# Master_2.net
KiCad netlist of a schematic drawn in Altium Designer
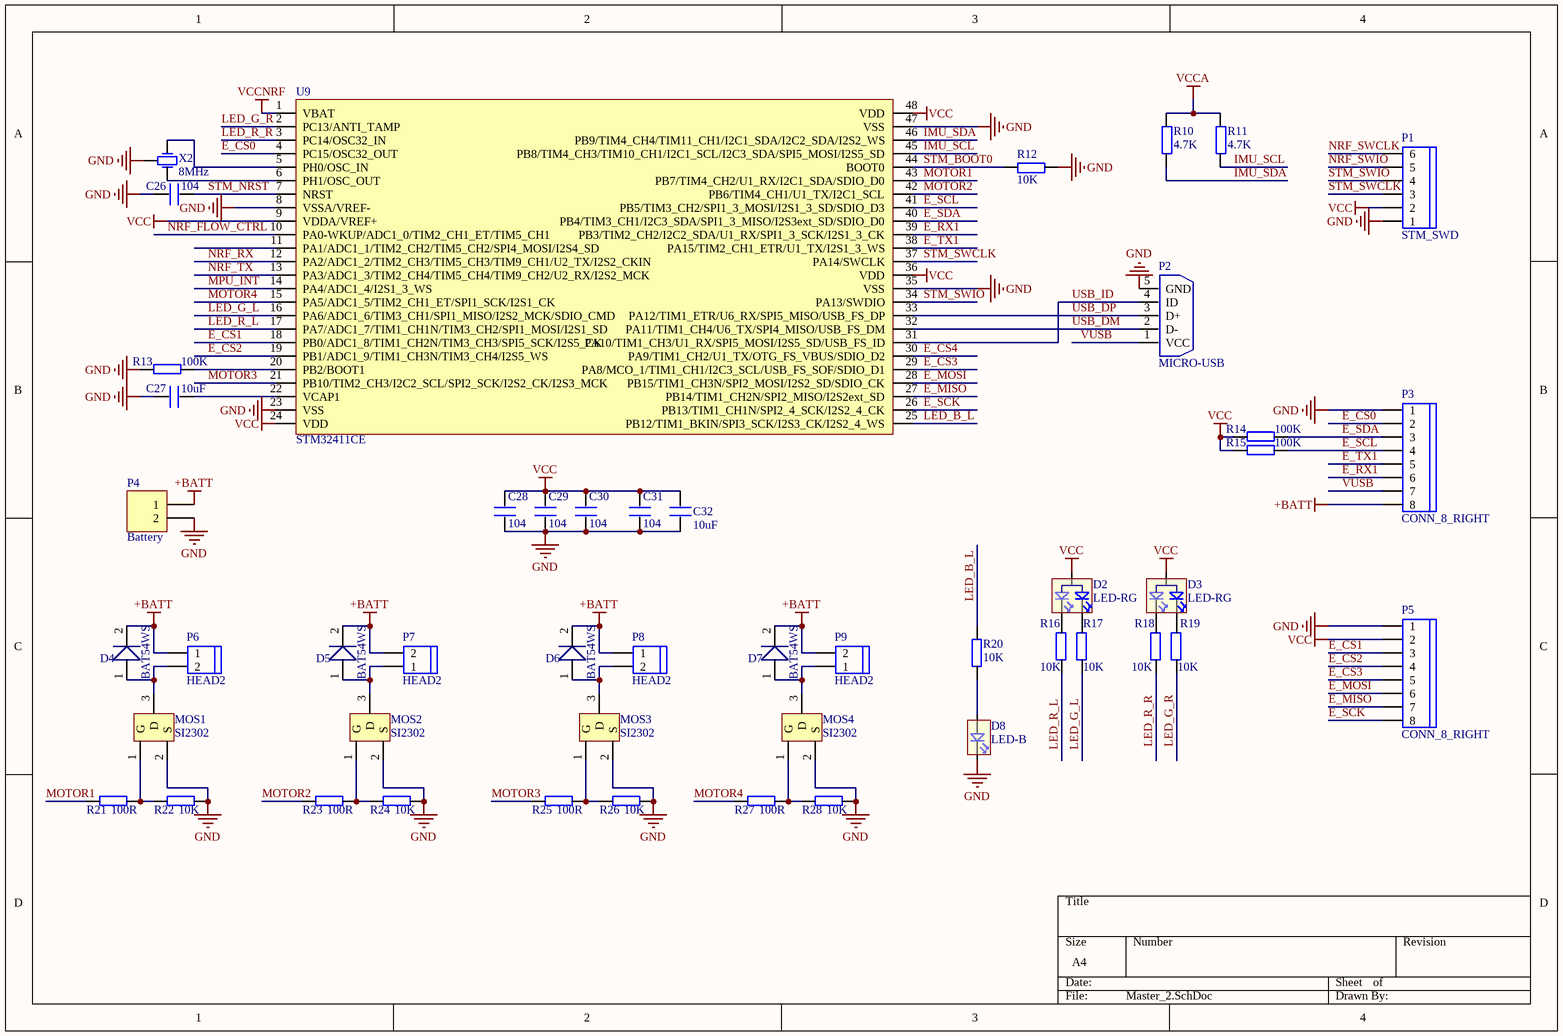
[diagram p0: Master_2.SchDoc]

(export (version "E")
  (design (tool "Eeschema 10.0.6"))
  (components
    (comp (ref "C26") (value "104") (footprint "0402") (libsource (lib "MiniFly ") (part "C")))
    (comp (ref "C27") (value "10uF") (footprint "0603P") (libsource (lib "MiniFly ") (part "C")))
    (comp (ref "C28") (value "104") (footprint "0402") (libsource (lib "MiniFly ") (part "C")))
    (comp (ref "C29") (value "104") (footprint "0402") (libsource (lib "MiniFly ") (part "C")))
    (comp (ref "C30") (value "104") (footprint "0402") (libsource (lib "MiniFly ") (part "C")))
    (comp (ref "C31") (value "104") (footprint "0402") (libsource (lib "MiniFly ") (part "C")))
    (comp (ref "C32") (value "10uF") (footprint "0603P") (libsource (lib "MiniFly ") (part "C")))
    (comp (ref "D2")
      (value "LED-RG")
      (footprint "LED1206  侧贴")
      (description "LED 1206 侧贴 双色")
      (libsource (lib "MiniFly ") (part "LED 1206 侧贴 双色"))
    )
    (comp (ref "D3")
      (value "LED-RG")
      (footprint "LED1206  侧贴")
      (description "LED 1206 侧贴 双色")
      (libsource (lib "MiniFly ") (part "LED 1206 侧贴 双色"))
    )
    (comp (ref "D4")
      (value "BAT54WS")
      (footprint "SOD-323")
      (description "单肖特基二极管")
      (libsource (lib "MiniFly ") (part "BAT54"))
    )
    (comp (ref "D5")
      (value "BAT54WS")
      (footprint "SOD-323")
      (description "单肖特基二极管")
      (libsource (lib "MiniFly ") (part "BAT54"))
    )
    (comp (ref "D6")
      (value "BAT54WS")
      (footprint "SOD-323")
      (description "单肖特基二极管")
      (libsource (lib "MiniFly ") (part "BAT54"))
    )
    (comp (ref "D7")
      (value "BAT54WS")
      (footprint "SOD-323")
      (description "单肖特基二极管")
      (libsource (lib "MiniFly ") (part "BAT54"))
    )
    (comp (ref "D8")
      (value "LED-B")
      (footprint "LED1206  侧贴")
      (description "LED 1206 侧贴  单色")
      (libsource (lib "MiniFly ") (part "LED 1206 侧贴  单色"))
    )
    (comp (ref "MOS1")
      (value "SI2302")
      (footprint "SO-G3/C2.5")
      (description "AP2306")
      (libsource (lib "MiniFly ") (part "MOS-N"))
    )
    (comp (ref "MOS2")
      (value "SI2302")
      (footprint "SO-G3/C2.5")
      (description "AP2306")
      (libsource (lib "MiniFly ") (part "MOS-N"))
    )
    (comp (ref "MOS3")
      (value "SI2302")
      (footprint "SO-G3/C2.5")
      (description "AP2306")
      (libsource (lib "MiniFly ") (part "MOS-N"))
    )
    (comp (ref "MOS4")
      (value "SI2302")
      (footprint "SO-G3/C2.5")
      (description "AP2306")
      (libsource (lib "MiniFly ") (part "MOS-N"))
    )
    (comp (ref "P1") (value "STM_SWD") (footprint "SH1.0-6P") (libsource (lib "MiniFly ") (part "HEAD6")))
    (comp (ref "P2")
      (value "MICRO-USB")
      (footprint "MICRO_USB5P_SOP")
      (libsource (lib "MiniFly ") (part "USB5"))
    )
    (comp (ref "P3")
      (value "CONN_8_RIGHT")
      (footprint "HEADER8-2.0MM-SMD")
      (libsource (lib "MiniFly ") (part "HEAD8"))
    )
    (comp (ref "P4")
      (value "Battery")
      (footprint "HDR1X2")
      (description "Header, 2-Pin")
      (fields (field (name "PUBLISHER") "Altium Limited"))
      (libsource (lib "MiniFly ") (part "Header 2"))
    )
    (comp (ref "P5")
      (value "CONN_8_RIGHT")
      (footprint "HEADER8-2.0MM-SMD")
      (libsource (lib "MiniFly ") (part "HEAD8"))
    )
    (comp (ref "P6") (value "HEAD2") (footprint "HEADER2-1.25MM") (libsource (lib "MiniFly ") (part "HEAD2")))
    (comp (ref "P7") (value "HEAD2") (footprint "HEADER2-1.25MM") (libsource (lib "MiniFly ") (part "HEAD2")))
    (comp (ref "P8") (value "HEAD2") (footprint "HEADER2-1.25MM") (libsource (lib "MiniFly ") (part "HEAD2")))
    (comp (ref "P9") (value "HEAD2") (footprint "HEADER2-1.25MM") (libsource (lib "MiniFly ") (part "HEAD2")))
    (comp (ref "R10") (value "4.7K") (footprint "0402") (libsource (lib "MiniFly ") (part "R")))
    (comp (ref "R11") (value "4.7K") (footprint "0402") (libsource (lib "MiniFly ") (part "R")))
    (comp (ref "R12") (value "10K") (footprint "0402") (libsource (lib "MiniFly ") (part "R")))
    (comp (ref "R13") (value "100K") (footprint "0402") (libsource (lib "MiniFly ") (part "R")))
    (comp (ref "R14") (value "100K") (footprint "0402") (libsource (lib "MiniFly ") (part "R")))
    (comp (ref "R15") (value "100K") (footprint "0402") (libsource (lib "MiniFly ") (part "R")))
    (comp (ref "R16") (value "10K") (footprint "0402") (libsource (lib "MiniFly ") (part "R")))
    (comp (ref "R17") (value "10K") (footprint "0402") (libsource (lib "MiniFly ") (part "R")))
    (comp (ref "R18") (value "10K") (footprint "0402") (libsource (lib "MiniFly ") (part "R")))
    (comp (ref "R19") (value "10K") (footprint "0402") (libsource (lib "MiniFly ") (part "R")))
    (comp (ref "R20") (value "10K") (footprint "0402") (libsource (lib "MiniFly ") (part "R")))
    (comp (ref "R21") (value "100R") (footprint "0402") (libsource (lib "MiniFly ") (part "R")))
    (comp (ref "R22") (value "10K") (footprint "0402") (libsource (lib "MiniFly ") (part "R")))
    (comp (ref "R23") (value "100R") (footprint "0402") (libsource (lib "MiniFly ") (part "R")))
    (comp (ref "R24") (value "10K") (footprint "0402") (libsource (lib "MiniFly ") (part "R")))
    (comp (ref "R25") (value "100R") (footprint "0402") (libsource (lib "MiniFly ") (part "R")))
    (comp (ref "R26") (value "10K") (footprint "0402") (libsource (lib "MiniFly ") (part "R")))
    (comp (ref "R27") (value "100R") (footprint "0402") (libsource (lib "MiniFly ") (part "R")))
    (comp (ref "R28") (value "10K") (footprint "0402") (libsource (lib "MiniFly ") (part "R")))
    (comp (ref "U9")
      (value "STM32411CE")
      (footprint "UFQFPN48")
      (description "STM32411xC_xE")
      (libsource (lib "MiniFly ") (part "STM32F411xC_xE"))
    )
    (comp (ref "X2") (value "8MHz") (footprint "XTAL3215") (libsource (lib "MiniFly ") (part "XTAL-3215")))
  )
  (nets
    (net (code "1") (name "+BATT") (class "Default")
      (node (ref "D4") (pin "2") (pinfunction "2_2") (pintype "passive"))
      (node (ref "D5") (pin "2") (pinfunction "2_2") (pintype "passive"))
      (node (ref "D6") (pin "2") (pinfunction "2_2") (pintype "passive"))
      (node (ref "D7") (pin "2") (pinfunction "2_2") (pintype "passive"))
      (node (ref "P3") (pin "8") (pinfunction "8_8") (pintype "passive"))
      (node (ref "P4") (pin "1") (pinfunction "1_1") (pintype "passive"))
      (node (ref "P6") (pin "1") (pinfunction "1_1") (pintype "passive"))
      (node (ref "P7") (pin "2") (pinfunction "2_2") (pintype "passive"))
      (node (ref "P8") (pin "1") (pinfunction "1_1") (pintype "passive"))
      (node (ref "P9") (pin "2") (pinfunction "2_2") (pintype "passive"))
    )
    (net (code "2") (name "/E_CS0") (class "Default")
      (node (ref "P3") (pin "2") (pinfunction "2_2") (pintype "passive"))
      (node (ref "U9") (pin "4") (pinfunction "PC15/OSC32_OUT_4") (pintype "passive"))
    )
    (net (code "3") (name "/E_CS1") (class "Default")
      (node (ref "P5") (pin "3") (pinfunction "3_3") (pintype "passive"))
      (node (ref "U9") (pin "18") (pinfunction "PB0/ADC1_8/TIM1_CH2N/TIM3_CH3/SPI5_SCK/I2S5_CK_18") (pintype "passive"))
    )
    (net (code "4") (name "/E_CS2") (class "Default")
      (node (ref "P5") (pin "4") (pinfunction "4_4") (pintype "passive"))
      (node (ref "U9") (pin "19") (pinfunction "PB1/ADC1_9/TIM1_CH3N/TIM3_CH4/I2S5_WS_19") (pintype "passive"))
    )
    (net (code "5") (name "/E_CS3") (class "Default")
      (node (ref "P5") (pin "5") (pinfunction "5_5") (pintype "passive"))
      (node (ref "U9") (pin "29") (pinfunction "PA8/MCO_1/TIM1_CH1/I2C3_SCL/USB_FS_SOF/SDIO_D1_29") (pintype "passive"))
    )
    (net (code "6") (name "/E_CS4") (class "Default")
      (node (ref "U9") (pin "30") (pinfunction "PA9/TIM1_CH2/U1_TX/OTG_FS_VBUS/SDIO_D2_30") (pintype "passive"))
    )
    (net (code "7") (name "/E_MISO") (class "Default")
      (node (ref "P5") (pin "7") (pinfunction "7_7") (pintype "passive"))
      (node (ref "U9") (pin "27") (pinfunction "PB14/TIM1_CH2N/SPI2_MISO/I2S2ext_SD_27") (pintype "passive"))
    )
    (net (code "8") (name "/E_MOSI") (class "Default")
      (node (ref "P5") (pin "6") (pinfunction "6_6") (pintype "passive"))
      (node (ref "U9") (pin "28") (pinfunction "PB15/TIM1_CH3N/SPI2_MOSI/I2S2_SD/SDIO_CK_28") (pintype "passive"))
    )
    (net (code "9") (name "/E_RX1") (class "Default")
      (node (ref "P3") (pin "6") (pinfunction "6_6") (pintype "passive"))
      (node (ref "U9") (pin "39") (pinfunction "PB3/TIM2_CH2/I2C2_SDA/U1_RX/SPI1_3_SCK/I2S1_3_CK_39") (pintype "passive"))
    )
    (net (code "10") (name "/E_SCK") (class "Default")
      (node (ref "P5") (pin "8") (pinfunction "8_8") (pintype "passive"))
      (node (ref "U9") (pin "26") (pinfunction "PB13/TIM1_CH1N/SPI2_4_SCK/I2S2_4_CK_26") (pintype "passive"))
    )
    (net (code "11") (name "/E_SCL") (class "Default")
      (node (ref "P3") (pin "4") (pinfunction "4_4") (pintype "passive"))
      (node (ref "R15") (pin "1") (pintype "passive"))
      (node (ref "U9") (pin "41") (pinfunction "PB5/TIM3_CH2/SPI1_3_MOSI/I2S1_3_SD/SDIO_D3_41") (pintype "passive"))
    )
    (net (code "12") (name "/E_SDA") (class "Default")
      (node (ref "P3") (pin "3") (pinfunction "3_3") (pintype "passive"))
      (node (ref "R14") (pin "1") (pintype "passive"))
      (node (ref "U9") (pin "40") (pinfunction "PB4/TIM3_CH1/I2C3_SDA/SPI1_3_MISO/I2S3ext_SD/SDIO_D0_40") (pintype "passive"))
    )
    (net (code "13") (name "/E_TX1") (class "Default")
      (node (ref "P3") (pin "5") (pinfunction "5_5") (pintype "passive"))
      (node (ref "U9") (pin "38") (pinfunction "PA15/TIM2_CH1_ETR/U1_TX/I2S1_3_WS_38") (pintype "passive"))
    )
    (net (code "14") (name "/IMU_SCL") (class "Default")
      (node (ref "R11") (pin "1") (pintype "passive"))
      (node (ref "U9") (pin "45") (pinfunction "PB8/TIM4_CH3/TIM10_CH1/I2C1_SCL/I2C3_SDA/SPI5_MOSI/I2S5_SD_45") (pintype "passive"))
    )
    (net (code "15") (name "/IMU_SDA") (class "Default")
      (node (ref "R10") (pin "1") (pintype "passive"))
      (node (ref "U9") (pin "46") (pinfunction "PB9/TIM4_CH4/TIM11_CH1/I2C1_SDA/I2C2_SDA/I2S2_WS_46") (pintype "passive"))
    )
    (net (code "16") (name "/LED_B_L") (class "Default")
      (node (ref "R20") (pin "1") (pintype "passive"))
      (node (ref "U9") (pin "25") (pinfunction "PB12/TIM1_BKIN/SPI3_SCK/I2S3_CK/I2S2_4_WS_25") (pintype "passive"))
    )
    (net (code "17") (name "/LED_G_L") (class "Default")
      (node (ref "R17") (pin "2") (pintype "passive"))
      (node (ref "U9") (pin "16") (pinfunction "PA6/ADC1_6/TIM3_CH1/SPI1_MISO/I2S2_MCK/SDIO_CMD_16") (pintype "passive"))
    )
    (net (code "18") (name "/LED_G_R") (class "Default")
      (node (ref "R19") (pin "2") (pintype "passive"))
      (node (ref "U9") (pin "2") (pinfunction "PC13/ANTI_TAMP_2") (pintype "passive"))
    )
    (net (code "19") (name "/LED_R_L") (class "Default")
      (node (ref "R16") (pin "2") (pintype "passive"))
      (node (ref "U9") (pin "17") (pinfunction "PA7/ADC1_7/TIM1_CH1N/TIM3_CH2/SPI1_MOSI/I2S1_SD_17") (pintype "passive"))
    )
    (net (code "20") (name "/LED_R_R") (class "Default")
      (node (ref "R18") (pin "2") (pintype "passive"))
      (node (ref "U9") (pin "3") (pinfunction "PC14/OSC32_IN_3") (pintype "passive"))
    )
    (net (code "21") (name "/MOTOR1") (class "Default")
      (node (ref "R21") (pin "2") (pintype "passive"))
      (node (ref "U9") (pin "43") (pinfunction "PB7/TIM4_CH2/U1_RX/I2C1_SDA/SDIO_D0_43") (pintype "passive"))
    )
    (net (code "22") (name "/MOTOR2") (class "Default")
      (node (ref "R23") (pin "2") (pintype "passive"))
      (node (ref "U9") (pin "42") (pinfunction "PB6/TIM4_CH1/U1_TX/I2C1_SCL_42") (pintype "passive"))
    )
    (net (code "23") (name "/MOTOR3") (class "Default")
      (node (ref "R25") (pin "2") (pintype "passive"))
      (node (ref "U9") (pin "21") (pinfunction "PB10/TIM2_CH3/I2C2_SCL/SPI2_SCK/I2S2_CK/I2S3_MCK_21") (pintype "passive"))
    )
    (net (code "24") (name "/MOTOR4") (class "Default")
      (node (ref "R27") (pin "2") (pintype "passive"))
      (node (ref "U9") (pin "15") (pinfunction "PA5/ADC1_5/TIM2_CH1_ET/SPI1_SCK/I2S1_CK_15") (pintype "passive"))
    )
    (net (code "25") (name "/MPU_INT") (class "Default")
      (node (ref "U9") (pin "14") (pinfunction "PA4/ADC1_4/I2S1_3_WS_14") (pintype "passive"))
    )
    (net (code "26") (name "/NRF_FLOW_CTRL") (class "Default")
      (node (ref "U9") (pin "10") (pinfunction "PA0-WKUP/ADC1_0/TIM2_CH1_ET/TIM5_CH1_10") (pintype "passive"))
    )
    (net (code "27") (name "/NRF_RX") (class "Default")
      (node (ref "U9") (pin "12") (pinfunction "PA2/ADC1_2/TIM2_CH3/TIM5_CH3/TIM9_CH1/U2_TX/I2S2_CKIN_12") (pintype "passive"))
    )
    (net (code "28") (name "/NRF_SWCLK") (class "Default")
      (node (ref "P1") (pin "6") (pinfunction "6_6") (pintype "passive"))
    )
    (net (code "29") (name "/NRF_SWIO") (class "Default")
      (node (ref "P1") (pin "5") (pinfunction "5_5") (pintype "passive"))
    )
    (net (code "30") (name "/NRF_TX") (class "Default")
      (node (ref "U9") (pin "13") (pinfunction "PA3/ADC1_3/TIM2_CH4/TIM5_CH4/TIM9_CH2/U2_RX/I2S2_MCK_13") (pintype "passive"))
    )
    (net (code "31") (name "/STM_BOOT0") (class "Default")
      (node (ref "R12") (pin "1") (pintype "passive"))
      (node (ref "U9") (pin "44") (pinfunction "BOOT0_44") (pintype "passive"))
    )
    (net (code "32") (name "/STM_NRST") (class "Default")
      (node (ref "C26") (pin "2") (pintype "passive"))
      (node (ref "U9") (pin "7") (pinfunction "NRST_7") (pintype "passive"))
    )
    (net (code "33") (name "/STM_SWCLK") (class "Default")
      (node (ref "P1") (pin "3") (pinfunction "3_3") (pintype "passive"))
      (node (ref "U9") (pin "37") (pinfunction "PA14/SWCLK_37") (pintype "passive"))
    )
    (net (code "34") (name "/STM_SWIO") (class "Default")
      (node (ref "P1") (pin "4") (pinfunction "4_4") (pintype "passive"))
      (node (ref "U9") (pin "34") (pinfunction "PA13/SWDIO_34") (pintype "passive"))
    )
    (net (code "35") (name "/USB_DM") (class "Default")
      (node (ref "P2") (pin "2") (pinfunction "D-_2") (pintype "passive"))
      (node (ref "U9") (pin "32") (pinfunction "PA11/TIM1_CH4/U6_TX/SPI4_MISO/USB_FS_DM_32") (pintype "passive"))
    )
    (net (code "36") (name "/USB_DP") (class "Default")
      (node (ref "P2") (pin "3") (pinfunction "D+_3") (pintype "passive"))
      (node (ref "U9") (pin "33") (pinfunction "PA12/TIM1_ETR/U6_RX/SPI5_MISO/USB_FS_DP_33") (pintype "passive"))
    )
    (net (code "37") (name "/USB_ID") (class "Default")
      (node (ref "P2") (pin "4") (pinfunction "ID_4") (pintype "passive"))
      (node (ref "U9") (pin "31") (pinfunction "PA10/TIM1_CH3/U1_RX/SPI5_MOSI/I2S5_SD/USB_FS_ID_31") (pintype "passive"))
    )
    (net (code "38") (name "/VUSB") (class "Default")
      (node (ref "P2") (pin "1") (pinfunction "VCC_1") (pintype "passive"))
      (node (ref "P3") (pin "7") (pinfunction "7_7") (pintype "passive"))
    )
    (net (code "39") (name "GND") (class "Default")
      (node (ref "C26") (pin "1") (pintype "passive"))
      (node (ref "C27") (pin "1") (pintype "passive"))
      (node (ref "C28") (pin "1") (pintype "passive"))
      (node (ref "C29") (pin "1") (pintype "passive"))
      (node (ref "C30") (pin "1") (pintype "passive"))
      (node (ref "C31") (pin "1") (pintype "passive"))
      (node (ref "C32") (pin "1") (pintype "passive"))
      (node (ref "D8") (pin "1") (pinfunction "1_1") (pintype "passive"))
      (node (ref "MOS1") (pin "2") (pinfunction "S_2") (pintype "passive"))
      (node (ref "MOS2") (pin "2") (pinfunction "S_2") (pintype "passive"))
      (node (ref "MOS3") (pin "2") (pinfunction "S_2") (pintype "passive"))
      (node (ref "MOS4") (pin "2") (pinfunction "S_2") (pintype "passive"))
      (node (ref "P1") (pin "1") (pinfunction "1_1") (pintype "passive"))
      (node (ref "P2") (pin "5") (pinfunction "GND_5") (pintype "passive"))
      (node (ref "P3") (pin "1") (pinfunction "1_1") (pintype "passive"))
      (node (ref "P4") (pin "2") (pinfunction "2_2") (pintype "passive"))
      (node (ref "P5") (pin "1") (pinfunction "1_1") (pintype "passive"))
      (node (ref "R12") (pin "2") (pintype "passive"))
      (node (ref "R13") (pin "2") (pintype "passive"))
      (node (ref "R22") (pin "1") (pintype "passive"))
      (node (ref "R24") (pin "1") (pintype "passive"))
      (node (ref "R26") (pin "1") (pintype "passive"))
      (node (ref "R28") (pin "1") (pintype "passive"))
      (node (ref "U9") (pin "23") (pinfunction "VSS_23") (pintype "passive"))
      (node (ref "U9") (pin "35") (pinfunction "VSS_35") (pintype "passive"))
      (node (ref "U9") (pin "47") (pinfunction "VSS_47") (pintype "passive"))
      (node (ref "U9") (pin "8") (pinfunction "VSSA/VREF-_8") (pintype "passive"))
      (node (ref "X2") (pin "2") (pinfunction "GND_2") (pintype "passive"))
    )
    (net (code "40") (name "Net-(D2-Pad1)") (class "Default")
      (node (ref "D2") (pin "1") (pinfunction "1_1") (pintype "passive"))
      (node (ref "R16") (pin "1") (pintype "passive"))
    )
    (net (code "41") (name "Net-(D2-Pad2)") (class "Default")
      (node (ref "D2") (pin "2") (pinfunction "2_2") (pintype "passive"))
      (node (ref "R17") (pin "1") (pintype "passive"))
    )
    (net (code "42") (name "Net-(D3-Pad1)") (class "Default")
      (node (ref "D3") (pin "1") (pinfunction "1_1") (pintype "passive"))
      (node (ref "R18") (pin "1") (pintype "passive"))
    )
    (net (code "43") (name "Net-(D3-Pad2)") (class "Default")
      (node (ref "D3") (pin "2") (pinfunction "2_2") (pintype "passive"))
      (node (ref "R19") (pin "1") (pintype "passive"))
    )
    (net (code "44") (name "Net-(D8-Pad3)") (class "Default")
      (node (ref "D8") (pin "3") (pinfunction "3_3") (pintype "passive"))
      (node (ref "R20") (pin "2") (pintype "passive"))
    )
    (net (code "45") (name "Net-(MOS1-D)") (class "Default")
      (node (ref "D4") (pin "1") (pinfunction "1_1") (pintype "passive"))
      (node (ref "MOS1") (pin "3") (pinfunction "D_3") (pintype "passive"))
      (node (ref "P6") (pin "2") (pinfunction "2_2") (pintype "passive"))
    )
    (net (code "46") (name "Net-(MOS1-G)") (class "Default")
      (node (ref "MOS1") (pin "1") (pinfunction "G_1") (pintype "passive"))
      (node (ref "R21") (pin "1") (pintype "passive"))
      (node (ref "R22") (pin "2") (pintype "passive"))
    )
    (net (code "47") (name "Net-(MOS2-D)") (class "Default")
      (node (ref "D5") (pin "1") (pinfunction "1_1") (pintype "passive"))
      (node (ref "MOS2") (pin "3") (pinfunction "D_3") (pintype "passive"))
      (node (ref "P7") (pin "1") (pinfunction "1_1") (pintype "passive"))
    )
    (net (code "48") (name "Net-(MOS2-G)") (class "Default")
      (node (ref "MOS2") (pin "1") (pinfunction "G_1") (pintype "passive"))
      (node (ref "R23") (pin "1") (pintype "passive"))
      (node (ref "R24") (pin "2") (pintype "passive"))
    )
    (net (code "49") (name "Net-(MOS3-D)") (class "Default")
      (node (ref "D6") (pin "1") (pinfunction "1_1") (pintype "passive"))
      (node (ref "MOS3") (pin "3") (pinfunction "D_3") (pintype "passive"))
      (node (ref "P8") (pin "2") (pinfunction "2_2") (pintype "passive"))
    )
    (net (code "50") (name "Net-(MOS3-G)") (class "Default")
      (node (ref "MOS3") (pin "1") (pinfunction "G_1") (pintype "passive"))
      (node (ref "R25") (pin "1") (pintype "passive"))
      (node (ref "R26") (pin "2") (pintype "passive"))
    )
    (net (code "51") (name "Net-(MOS4-D)") (class "Default")
      (node (ref "D7") (pin "1") (pinfunction "1_1") (pintype "passive"))
      (node (ref "MOS4") (pin "3") (pinfunction "D_3") (pintype "passive"))
      (node (ref "P9") (pin "1") (pinfunction "1_1") (pintype "passive"))
    )
    (net (code "52") (name "Net-(MOS4-G)") (class "Default")
      (node (ref "MOS4") (pin "1") (pinfunction "G_1") (pintype "passive"))
      (node (ref "R27") (pin "1") (pintype "passive"))
      (node (ref "R28") (pin "2") (pintype "passive"))
    )
    (net (code "53") (name "Net-(U9-PB2{slash}BOOT1)") (class "Default")
      (node (ref "R13") (pin "1") (pintype "passive"))
      (node (ref "U9") (pin "20") (pinfunction "PB2/BOOT1_20") (pintype "passive"))
    )
    (net (code "54") (name "Net-(U9-PH0{slash}OSC_IN)") (class "Default")
      (node (ref "U9") (pin "5") (pinfunction "PH0/OSC_IN_5") (pintype "passive"))
      (node (ref "X2") (pin "1") (pinfunction "OSC1_1") (pintype "passive"))
    )
    (net (code "55") (name "Net-(U9-PH1{slash}OSC_OUT)") (class "Default")
      (node (ref "U9") (pin "6") (pinfunction "PH1/OSC_OUT_6") (pintype "passive"))
      (node (ref "X2") (pin "3") (pinfunction "OSC2_3") (pintype "passive"))
    )
    (net (code "56") (name "Net-(U9-VCAP1)") (class "Default")
      (node (ref "C27") (pin "2") (pintype "passive"))
      (node (ref "U9") (pin "22") (pinfunction "VCAP1_22") (pintype "passive"))
    )
    (net (code "57") (name "VCC") (class "Default")
      (node (ref "C28") (pin "2") (pintype "passive"))
      (node (ref "C29") (pin "2") (pintype "passive"))
      (node (ref "C30") (pin "2") (pintype "passive"))
      (node (ref "C31") (pin "2") (pintype "passive"))
      (node (ref "C32") (pin "2") (pintype "passive"))
      (node (ref "D2") (pin "3") (pinfunction "3_3") (pintype "passive"))
      (node (ref "D3") (pin "3") (pinfunction "3_3") (pintype "passive"))
      (node (ref "P1") (pin "2") (pinfunction "2_2") (pintype "passive"))
      (node (ref "P5") (pin "2") (pinfunction "2_2") (pintype "passive"))
      (node (ref "R14") (pin "2") (pintype "passive"))
      (node (ref "R15") (pin "2") (pintype "passive"))
      (node (ref "U9") (pin "24") (pinfunction "VDD_24") (pintype "passive"))
      (node (ref "U9") (pin "36") (pinfunction "VDD_36") (pintype "passive"))
      (node (ref "U9") (pin "48") (pinfunction "VDD_48") (pintype "passive"))
      (node (ref "U9") (pin "9") (pinfunction "VDDA/VREF+_9") (pintype "passive"))
    )
    (net (code "58") (name "VCCA") (class "Default")
      (node (ref "R10") (pin "2") (pintype "passive"))
      (node (ref "R11") (pin "2") (pintype "passive"))
    )
    (net (code "59") (name "VCCNRF") (class "Default")
      (node (ref "U9") (pin "1") (pinfunction "VBAT_1") (pintype "passive"))
    )
    (net (code "60") (name "unconnected-(D8-Pad2)") (class "Default")
      (node (ref "D8") (pin "2") (pinfunction "2_2") (pintype "passive"))
    )
    (net (code "61") (name "unconnected-(U9-PA1{slash}ADC1_1{slash}TIM2_CH2{slash}TIM5_CH2{slash}SPI4_MOSI{slash}I2S4_SD-Pad11)") (class "Default")
      (node (ref "U9") (pin "11") (pinfunction "PA1/ADC1_1/TIM2_CH2/TIM5_CH2/SPI4_MOSI/I2S4_SD_11") (pintype "passive"))
    )
  )
)
